# AlphaProtoRev3.net
KiCad netlist of a schematic drawn in EAGLE
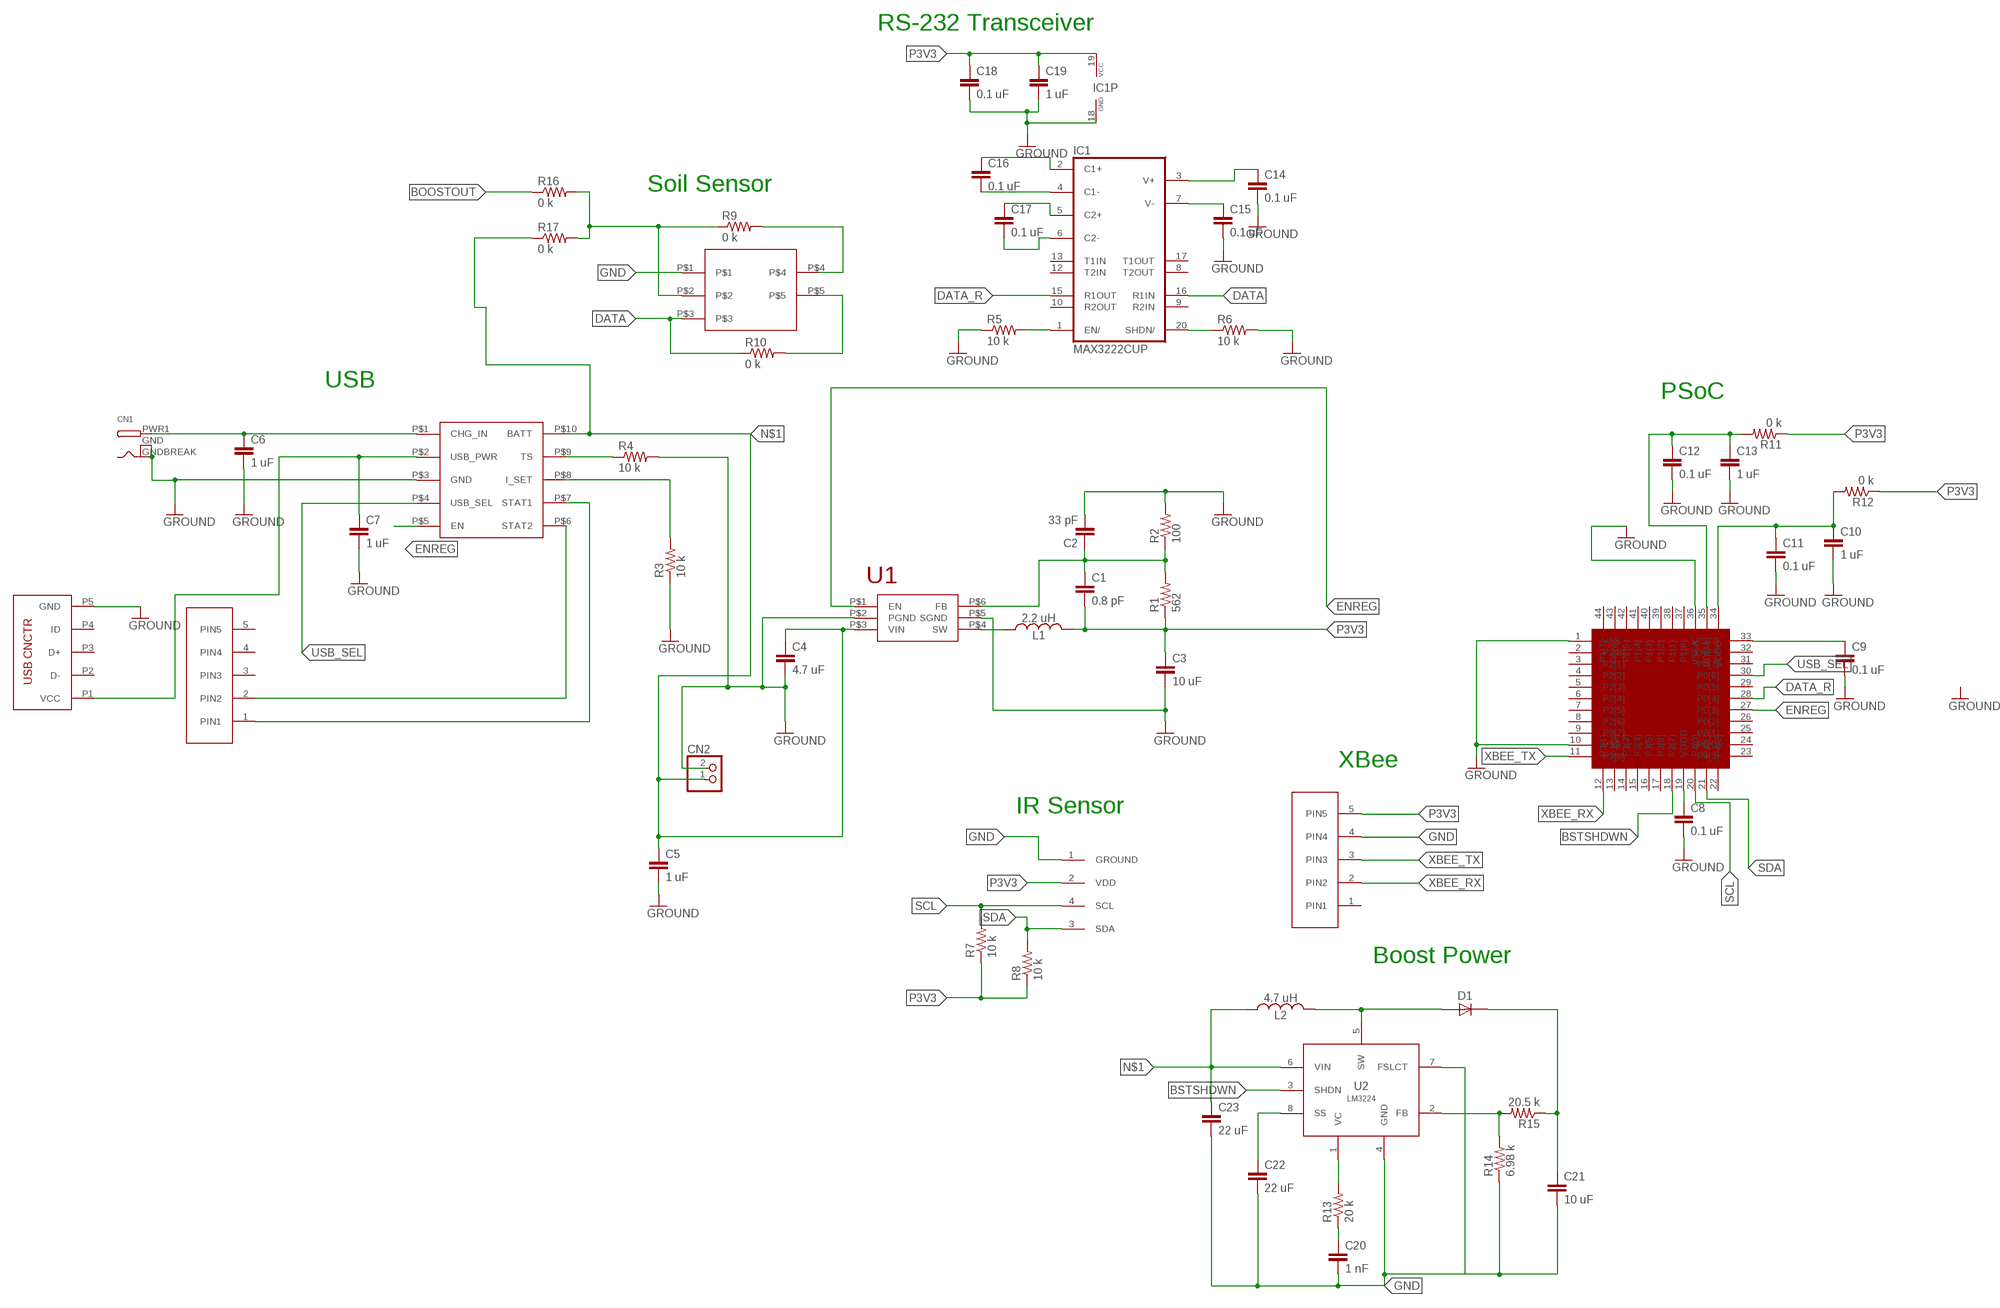
[diagram p0: schematic, sheet 1]

(export (version "E")
  (design (tool "Eeschema 10.0.6"))
  (components
    (comp (ref "C1")
      (value "0.8 pF")
      (footprint "eagle-import:0603")
      (libsource (lib "eagle-import") (part "CAPACITOR0603"))
    )
    (comp (ref "C2")
      (value "33 pF")
      (footprint "eagle-import:0603")
      (libsource (lib "eagle-import") (part "CAPACITOR0603"))
    )
    (comp (ref "C3")
      (value "10 uF")
      (footprint "eagle-import:0603")
      (libsource (lib "eagle-import") (part "CAPACITOR0603"))
    )
    (comp (ref "C4")
      (value "4.7 uF")
      (footprint "eagle-import:0603")
      (libsource (lib "eagle-import") (part "CAPACITOR0603"))
    )
    (comp (ref "C5")
      (value "1 uF")
      (footprint "eagle-import:0603")
      (libsource (lib "eagle-import") (part "CAPACITOR0603"))
    )
    (comp (ref "C6")
      (value "1 uF")
      (footprint "eagle-import:0603")
      (libsource (lib "eagle-import") (part "CAPACITOR0603"))
    )
    (comp (ref "C7")
      (value "1 uF")
      (footprint "eagle-import:0603")
      (libsource (lib "eagle-import") (part "CAPACITOR0603"))
    )
    (comp (ref "C8")
      (value "0.1 uF")
      (footprint "eagle-import:0603")
      (libsource (lib "eagle-import") (part "CAPACITOR0603"))
    )
    (comp (ref "C9")
      (value "0.1 uF")
      (footprint "eagle-import:0603")
      (libsource (lib "eagle-import") (part "CAPACITOR0603"))
    )
    (comp (ref "C10")
      (value "1 uF")
      (footprint "eagle-import:0603")
      (libsource (lib "eagle-import") (part "CAPACITOR0603"))
    )
    (comp (ref "C11")
      (value "0.1 uF")
      (footprint "eagle-import:0603")
      (libsource (lib "eagle-import") (part "CAPACITOR0603"))
    )
    (comp (ref "C12")
      (value "0.1 uF")
      (footprint "eagle-import:0603")
      (libsource (lib "eagle-import") (part "CAPACITOR0603"))
    )
    (comp (ref "C13")
      (value "1 uF")
      (footprint "eagle-import:0603")
      (libsource (lib "eagle-import") (part "CAPACITOR0603"))
    )
    (comp (ref "C14")
      (value "0.1 uF")
      (footprint "eagle-import:0603")
      (libsource (lib "eagle-import") (part "CAPACITOR0603"))
    )
    (comp (ref "C15")
      (value "0.1 uF")
      (footprint "eagle-import:0603")
      (libsource (lib "eagle-import") (part "CAPACITOR0603"))
    )
    (comp (ref "C16")
      (value "0.1 uF")
      (footprint "eagle-import:0603")
      (libsource (lib "eagle-import") (part "CAPACITOR0603"))
    )
    (comp (ref "C17")
      (value "0.1 uF")
      (footprint "eagle-import:0603")
      (libsource (lib "eagle-import") (part "CAPACITOR0603"))
    )
    (comp (ref "C18")
      (value "0.1 uF")
      (footprint "eagle-import:0603")
      (libsource (lib "eagle-import") (part "CAPACITOR0603"))
    )
    (comp (ref "C19")
      (value "1 uF")
      (footprint "eagle-import:0603")
      (libsource (lib "eagle-import") (part "CAPACITOR0603"))
    )
    (comp (ref "C20")
      (value "1 nF")
      (footprint "eagle-import:0603")
      (libsource (lib "eagle-import") (part "CAPACITOR0603"))
    )
    (comp (ref "C21")
      (value "10 uF")
      (footprint "eagle-import:0603")
      (libsource (lib "eagle-import") (part "CAPACITOR0603"))
    )
    (comp (ref "C22")
      (value "22 uF")
      (footprint "eagle-import:0603")
      (libsource (lib "eagle-import") (part "CAPACITOR0603"))
    )
    (comp (ref "C23")
      (value "22 uF")
      (footprint "eagle-import:0603")
      (libsource (lib "eagle-import") (part "CAPACITOR0603"))
    )
    (comp (ref "CN1")
      (value "DCBARRELSMT")
      (footprint "eagle-import:DCJACK_2MM_SMT")
      (libsource (lib "eagle-import") (part "DCBARRELSMT"))
    )
    (comp (ref "CN2")
      (value "JST_2PIN-SMT-RA")
      (footprint "eagle-import:JST-PH-2-SMT-RA")
      (libsource (lib "eagle-import") (part "JST_2PIN-SMT-RA"))
    )
    (comp (ref "D1")
      (value "DIODE")
      (footprint "eagle-import:0603-LED")
      (libsource (lib "eagle-import") (part "DIODE"))
    )
    (comp (ref "IC")
      (value "PSOC4FP")
      (footprint "eagle-import:TQFP44")
      (libsource (lib "eagle-import") (part "PSOC4FP"))
    )
    (comp (ref "IC1")
      (value "MAX3222CUP")
      (footprint "eagle-import:TSSOP20")
      (libsource (lib "eagle-import") (part "MAX3222CUP"))
    )
    (comp (ref "IRSENSOR")
      (value "TO39")
      (footprint "eagle-import:TO39")
      (libsource (lib "eagle-import") (part "TO39"))
    )
    (comp (ref "L1")
      (value "2.2 uH")
      (footprint "eagle-import:0603")
      (libsource (lib "eagle-import") (part "INDUCTOR0603"))
    )
    (comp (ref "L2")
      (value "4.7 uH")
      (footprint "eagle-import:0603")
      (libsource (lib "eagle-import") (part "INDUCTOR0603"))
    )
    (comp (ref "R1")
      (value "562")
      (footprint "eagle-import:0603")
      (libsource (lib "eagle-import") (part "RESISTOR0603"))
    )
    (comp (ref "R2")
      (value "100")
      (footprint "eagle-import:0603")
      (libsource (lib "eagle-import") (part "RESISTOR0603"))
    )
    (comp (ref "R3")
      (value "10 k")
      (footprint "eagle-import:0603")
      (libsource (lib "eagle-import") (part "RESISTOR0603"))
    )
    (comp (ref "R4")
      (value "10 k")
      (footprint "eagle-import:0603")
      (libsource (lib "eagle-import") (part "RESISTOR0603"))
    )
    (comp (ref "R5")
      (value "10 k")
      (footprint "eagle-import:0603")
      (libsource (lib "eagle-import") (part "RESISTOR0603"))
    )
    (comp (ref "R6")
      (value "10 k")
      (footprint "eagle-import:0603")
      (libsource (lib "eagle-import") (part "RESISTOR0603"))
    )
    (comp (ref "R7")
      (value "10 k")
      (footprint "eagle-import:0603")
      (libsource (lib "eagle-import") (part "RESISTOR0603"))
    )
    (comp (ref "R8")
      (value "10 k")
      (footprint "eagle-import:0603")
      (libsource (lib "eagle-import") (part "RESISTOR0603"))
    )
    (comp (ref "R9")
      (value "0 k")
      (footprint "eagle-import:0603")
      (libsource (lib "eagle-import") (part "RESISTOR0603"))
    )
    (comp (ref "R10")
      (value "0 k")
      (footprint "eagle-import:0603")
      (libsource (lib "eagle-import") (part "RESISTOR0603"))
    )
    (comp (ref "R11")
      (value "0 k")
      (footprint "eagle-import:0603")
      (libsource (lib "eagle-import") (part "RESISTOR0603"))
    )
    (comp (ref "R12")
      (value "0 k")
      (footprint "eagle-import:0603")
      (libsource (lib "eagle-import") (part "RESISTOR0603"))
    )
    (comp (ref "R13")
      (value "20 k")
      (footprint "eagle-import:0603")
      (libsource (lib "eagle-import") (part "RESISTOR0603"))
    )
    (comp (ref "R14")
      (value "6.98 k")
      (footprint "eagle-import:0603")
      (libsource (lib "eagle-import") (part "RESISTOR0603"))
    )
    (comp (ref "R15")
      (value "20.5 k")
      (footprint "eagle-import:0603")
      (libsource (lib "eagle-import") (part "RESISTOR0603"))
    )
    (comp (ref "R16")
      (value "0 k")
      (footprint "eagle-import:0603")
      (libsource (lib "eagle-import") (part "RESISTOR0603"))
    )
    (comp (ref "R17")
      (value "0 k")
      (footprint "eagle-import:0603")
      (libsource (lib "eagle-import") (part "RESISTOR0603"))
    )
    (comp (ref "U$2")
      (value "AUDIOJACK")
      (footprint "eagle-import:AUDIOJACK")
      (libsource (lib "eagle-import") (part "AUDIOJACK"))
    )
    (comp (ref "U$4")
      (value "LM3658")
      (footprint "eagle-import:LM3658")
      (libsource (lib "eagle-import") (part "LM3658"))
    )
    (comp (ref "U$7")
      (value "FCI10118192-0001LF")
      (footprint "eagle-import:FCI10118192-0001LF")
      (libsource (lib "eagle-import") (part "FCI10118192-0001LF"))
    )
    (comp (ref "U1")
      (value "LM3671-407564")
      (footprint "eagle-import:LM3671-407564")
      (libsource (lib "eagle-import") (part "LM3671-407564"))
    )
    (comp (ref "U2")
      (value "LM3224")
      (footprint "eagle-import:MSOP-8")
      (libsource (lib "eagle-import") (part "LM3224"))
    )
    (comp (ref "USB")
      (value "HEADER-5")
      (footprint "eagle-import:NON-5")
      (libsource (lib "eagle-import") (part "HEADER-5"))
    )
    (comp (ref "XBEE")
      (value "HEADER-5")
      (footprint "eagle-import:NON-5")
      (libsource (lib "eagle-import") (part "HEADER-5"))
    )
  )
  (nets
    (net (code "1") (name "BOOSTOUT") (class "Default")
      (node (ref "C21") (pin "1") (pinfunction "1_1") (pintype "passive"))
      (node (ref "D1") (pin "C") (pinfunction "C_C") (pintype "passive"))
      (node (ref "R15") (pin "1") (pinfunction "1_1") (pintype "passive"))
      (node (ref "R16") (pin "1") (pinfunction "1_1") (pintype "passive"))
    )
    (net (code "2") (name "BSTSHDWN") (class "Default")
      (node (ref "IC") (pin "18") (pinfunction "P3[7]_18") (pintype "bidirectional"))
      (node (ref "U2") (pin "3") (pinfunction "SHDN_3") (pintype "bidirectional"))
    )
    (net (code "3") (name "DATA") (class "Default")
      (node (ref "IC1") (pin "16") (pinfunction "R1IN_16") (pintype "input"))
      (node (ref "R10") (pin "1") (pinfunction "1_1") (pintype "passive"))
      (node (ref "U$2") (pin "P$3") (pinfunction "P$3_P$3") (pintype "output"))
    )
    (net (code "4") (name "DATA_R") (class "Default")
      (node (ref "IC") (pin "28") (pinfunction "P0[4]_28") (pintype "bidirectional"))
      (node (ref "IC1") (pin "15") (pinfunction "R1OUT_15") (pintype "output"))
    )
    (net (code "5") (name "ENREG") (class "Default")
      (node (ref "IC") (pin "27") (pinfunction "P0[3]_27") (pintype "bidirectional"))
      (node (ref "U$4") (pin "P$5") (pinfunction "EN_P$5") (pintype "input"))
      (node (ref "U1") (pin "P$1") (pinfunction "EN_P$1") (pintype "bidirectional"))
    )
    (net (code "6") (name "GND") (class "Default")
      (node (ref "C10") (pin "2") (pinfunction "2_2") (pintype "passive"))
      (node (ref "C11") (pin "2") (pinfunction "2_2") (pintype "passive"))
      (node (ref "C12") (pin "2") (pinfunction "2_2") (pintype "passive"))
      (node (ref "C13") (pin "2") (pinfunction "2_2") (pintype "passive"))
      (node (ref "C14") (pin "2") (pinfunction "2_2") (pintype "passive"))
      (node (ref "C15") (pin "2") (pinfunction "2_2") (pintype "passive"))
      (node (ref "C18") (pin "2") (pinfunction "2_2") (pintype "passive"))
      (node (ref "C19") (pin "2") (pinfunction "2_2") (pintype "passive"))
      (node (ref "C2") (pin "2") (pinfunction "2_2") (pintype "passive"))
      (node (ref "C20") (pin "2") (pinfunction "2_2") (pintype "passive"))
      (node (ref "C21") (pin "2") (pinfunction "2_2") (pintype "passive"))
      (node (ref "C22") (pin "2") (pinfunction "2_2") (pintype "passive"))
      (node (ref "C23") (pin "2") (pinfunction "2_2") (pintype "passive"))
      (node (ref "C3") (pin "2") (pinfunction "2_2") (pintype "passive"))
      (node (ref "C4") (pin "2") (pinfunction "2_2") (pintype "passive"))
      (node (ref "C5") (pin "2") (pinfunction "2_2") (pintype "passive"))
      (node (ref "C6") (pin "2") (pinfunction "2_2") (pintype "passive"))
      (node (ref "C7") (pin "2") (pinfunction "2_2") (pintype "passive"))
      (node (ref "C8") (pin "2") (pinfunction "2_2") (pintype "passive"))
      (node (ref "C9") (pin "2") (pinfunction "2_2") (pintype "passive"))
      (node (ref "CN1") (pin "GND") (pinfunction "GNDBREAK_GND") (pintype "power_in"))
      (node (ref "CN1") (pin "GNDBREAK") (pinfunction "GND_GNDBREAK") (pintype "power_in"))
      (node (ref "CN2") (pin "2") (pinfunction "1_2") (pintype "passive"))
      (node (ref "IC") (pin "1") (pinfunction "VSS_1") (pintype "bidirectional"))
      (node (ref "IC") (pin "10") (pinfunction "VSS_10") (pintype "bidirectional"))
      (node (ref "IC") (pin "36") (pinfunction "VSSA_36") (pintype "bidirectional"))
      (node (ref "IC1") (pin "18") (pinfunction "GND_18") (pintype "power_in"))
      (node (ref "IRSENSOR") (pin "1") (pinfunction "GROUND_1") (pintype "bidirectional"))
      (node (ref "R14") (pin "1") (pinfunction "1_1") (pintype "passive"))
      (node (ref "R2") (pin "2") (pinfunction "2_2") (pintype "passive"))
      (node (ref "R3") (pin "1") (pinfunction "1_1") (pintype "passive"))
      (node (ref "R4") (pin "2") (pinfunction "2_2") (pintype "passive"))
      (node (ref "R5") (pin "1") (pinfunction "1_1") (pintype "passive"))
      (node (ref "R6") (pin "2") (pinfunction "2_2") (pintype "passive"))
      (node (ref "U$2") (pin "P$1") (pinfunction "P$1_P$1") (pintype "output"))
      (node (ref "U$4") (pin "P$3") (pinfunction "GND_P$3") (pintype "power_in"))
      (node (ref "U$7") (pin "P5") (pinfunction "GND_P5") (pintype "power_in"))
      (node (ref "U1") (pin "P$2") (pinfunction "PGND_P$2") (pintype "passive"))
      (node (ref "U1") (pin "P$5") (pinfunction "SGND_P$5") (pintype "power_in"))
      (node (ref "U2") (pin "4") (pinfunction "GND_4") (pintype "bidirectional"))
      (node (ref "U2") (pin "7") (pinfunction "FSLCT_7") (pintype "bidirectional"))
      (node (ref "XBEE") (pin "4") (pinfunction "PIN4_4") (pintype "bidirectional"))
    )
    (net (code "7") (name "N$1") (class "Default")
      (node (ref "C23") (pin "1") (pinfunction "1_1") (pintype "passive"))
      (node (ref "C4") (pin "1") (pinfunction "1_1") (pintype "passive"))
      (node (ref "C5") (pin "1") (pinfunction "1_1") (pintype "passive"))
      (node (ref "CN2") (pin "1") (pinfunction "2_1") (pintype "passive"))
      (node (ref "L2") (pin "1") (pinfunction "1_1") (pintype "passive"))
      (node (ref "R17") (pin "1") (pinfunction "1_1") (pintype "passive"))
      (node (ref "U$4") (pin "P$10") (pinfunction "BATT_P$10") (pintype "power_in"))
      (node (ref "U1") (pin "P$3") (pinfunction "VIN_P$3") (pintype "power_in"))
      (node (ref "U2") (pin "6") (pinfunction "VIN_6") (pintype "bidirectional"))
    )
    (net (code "8") (name "Net-(C8-Pad1)") (class "Default")
      (node (ref "C8") (pin "1") (pinfunction "1_1") (pintype "passive"))
      (node (ref "IC") (pin "19") (pinfunction "VDDD_19") (pintype "bidirectional"))
    )
    (net (code "9") (name "Net-(C10-Pad1)") (class "Default")
      (node (ref "C10") (pin "1") (pinfunction "1_1") (pintype "passive"))
      (node (ref "C11") (pin "1") (pinfunction "1_1") (pintype "passive"))
      (node (ref "IC") (pin "34") (pinfunction "VDDD_34") (pintype "bidirectional"))
      (node (ref "R12") (pin "2") (pinfunction "2_2") (pintype "passive"))
    )
    (net (code "10") (name "Net-(C20-Pad1)") (class "Default")
      (node (ref "C20") (pin "1") (pinfunction "1_1") (pintype "passive"))
      (node (ref "R13") (pin "1") (pinfunction "1_1") (pintype "passive"))
    )
    (net (code "11") (name "Net-(CN1-PWR)") (class "Default")
      (node (ref "C6") (pin "1") (pinfunction "1_1") (pintype "passive"))
      (node (ref "CN1") (pin "PWR1") (pinfunction "PWR_PWR1") (pintype "power_in"))
      (node (ref "U$4") (pin "P$1") (pinfunction "CHG_IN_P$1") (pintype "power_in"))
    )
    (net (code "12") (name "Net-(IC-VCCD)") (class "Default")
      (node (ref "C9") (pin "1") (pinfunction "1_1") (pintype "passive"))
      (node (ref "IC") (pin "33") (pinfunction "VCCD_33") (pintype "bidirectional"))
    )
    (net (code "13") (name "Net-(IC-VDDA)") (class "Default")
      (node (ref "C12") (pin "1") (pinfunction "1_1") (pintype "passive"))
      (node (ref "C13") (pin "1") (pinfunction "1_1") (pintype "passive"))
      (node (ref "IC") (pin "35") (pinfunction "VDDA_35") (pintype "bidirectional"))
      (node (ref "R11") (pin "2") (pinfunction "2_2") (pintype "passive"))
    )
    (net (code "14") (name "Net-(IC1A-C1+)") (class "Default")
      (node (ref "C16") (pin "1") (pinfunction "1_1") (pintype "passive"))
      (node (ref "IC1") (pin "2") (pinfunction "C1+_2") (pintype "passive"))
    )
    (net (code "15") (name "Net-(IC1A-C1-)") (class "Default")
      (node (ref "C16") (pin "2") (pinfunction "2_2") (pintype "passive"))
      (node (ref "IC1") (pin "4") (pinfunction "C1-_4") (pintype "passive"))
    )
    (net (code "16") (name "Net-(IC1A-C2+)") (class "Default")
      (node (ref "C17") (pin "1") (pinfunction "1_1") (pintype "passive"))
      (node (ref "IC1") (pin "5") (pinfunction "C2+_5") (pintype "passive"))
    )
    (net (code "17") (name "Net-(IC1A-C2-)") (class "Default")
      (node (ref "C17") (pin "2") (pinfunction "2_2") (pintype "passive"))
      (node (ref "IC1") (pin "6") (pinfunction "C2-_6") (pintype "passive"))
    )
    (net (code "18") (name "Net-(IC1A-EN{slash})") (class "Default")
      (node (ref "IC1") (pin "1") (pinfunction "EN/_1") (pintype "input"))
      (node (ref "R5") (pin "2") (pinfunction "2_2") (pintype "passive"))
    )
    (net (code "19") (name "Net-(IC1A-SHDN{slash})") (class "Default")
      (node (ref "IC1") (pin "20") (pinfunction "SHDN/_20") (pintype "input"))
      (node (ref "R6") (pin "1") (pinfunction "1_1") (pintype "passive"))
    )
    (net (code "20") (name "Net-(IC1A-V+)") (class "Default")
      (node (ref "C14") (pin "1") (pinfunction "1_1") (pintype "passive"))
      (node (ref "IC1") (pin "3") (pinfunction "V+_3") (pintype "passive"))
    )
    (net (code "21") (name "Net-(IC1A-V-)") (class "Default")
      (node (ref "C15") (pin "1") (pinfunction "1_1") (pintype "passive"))
      (node (ref "IC1") (pin "7") (pinfunction "V-_7") (pintype "passive"))
    )
    (net (code "22") (name "Net-(R9-Pad2)") (class "Default")
      (node (ref "R9") (pin "2") (pinfunction "2_2") (pintype "passive"))
      (node (ref "U$2") (pin "P$4") (pinfunction "P$4_P$4") (pintype "output"))
    )
    (net (code "23") (name "Net-(R10-Pad2)") (class "Default")
      (node (ref "R10") (pin "2") (pinfunction "2_2") (pintype "passive"))
      (node (ref "U$2") (pin "P$5") (pinfunction "P$5_P$5") (pintype "output"))
    )
    (net (code "24") (name "Net-(R16-Pad2)") (class "Default")
      (node (ref "R16") (pin "2") (pinfunction "2_2") (pintype "passive"))
      (node (ref "R17") (pin "2") (pinfunction "2_2") (pintype "passive"))
      (node (ref "R9") (pin "1") (pinfunction "1_1") (pintype "passive"))
      (node (ref "U$2") (pin "P$2") (pinfunction "P$2_P$2") (pintype "output"))
    )
    (net (code "25") (name "Net-(U$4-I_SET)") (class "Default")
      (node (ref "R3") (pin "2") (pinfunction "2_2") (pintype "passive"))
      (node (ref "U$4") (pin "P$8") (pinfunction "I_SET_P$8") (pintype "bidirectional"))
    )
    (net (code "26") (name "Net-(U$4-STAT1)") (class "Default")
      (node (ref "U$4") (pin "P$7") (pinfunction "STAT1_P$7") (pintype "output"))
      (node (ref "USB") (pin "1") (pinfunction "PIN1_1") (pintype "bidirectional"))
    )
    (net (code "27") (name "Net-(U$4-STAT2)") (class "Default")
      (node (ref "U$4") (pin "P$6") (pinfunction "STAT2_P$6") (pintype "output"))
      (node (ref "USB") (pin "2") (pinfunction "PIN2_2") (pintype "bidirectional"))
    )
    (net (code "28") (name "Net-(U$4-TS)") (class "Default")
      (node (ref "R4") (pin "1") (pinfunction "1_1") (pintype "passive"))
      (node (ref "U$4") (pin "P$9") (pinfunction "TS_P$9") (pintype "bidirectional"))
    )
    (net (code "29") (name "Net-(U$4-USB_PWR)") (class "Default")
      (node (ref "C7") (pin "1") (pinfunction "1_1") (pintype "passive"))
      (node (ref "U$4") (pin "P$2") (pinfunction "USB_PWR_P$2") (pintype "power_in"))
      (node (ref "U$7") (pin "P1") (pinfunction "VCC_P1") (pintype "power_in"))
    )
    (net (code "30") (name "Net-(U1-FB)") (class "Default")
      (node (ref "C1") (pin "1") (pinfunction "1_1") (pintype "passive"))
      (node (ref "C2") (pin "1") (pinfunction "1_1") (pintype "passive"))
      (node (ref "R1") (pin "2") (pinfunction "2_2") (pintype "passive"))
      (node (ref "R2") (pin "1") (pinfunction "1_1") (pintype "passive"))
      (node (ref "U1") (pin "P$6") (pinfunction "FB_P$6") (pintype "bidirectional"))
    )
    (net (code "31") (name "Net-(U1-SW)") (class "Default")
      (node (ref "L1") (pin "1") (pinfunction "1_1") (pintype "passive"))
      (node (ref "U1") (pin "P$4") (pinfunction "SW_P$4") (pintype "bidirectional"))
    )
    (net (code "32") (name "Net-(U2-FB)") (class "Default")
      (node (ref "R14") (pin "2") (pinfunction "2_2") (pintype "passive"))
      (node (ref "R15") (pin "2") (pinfunction "2_2") (pintype "passive"))
      (node (ref "U2") (pin "2") (pinfunction "FB_2") (pintype "bidirectional"))
    )
    (net (code "33") (name "Net-(U2-SS)") (class "Default")
      (node (ref "C22") (pin "1") (pinfunction "1_1") (pintype "passive"))
      (node (ref "U2") (pin "8") (pinfunction "SS_8") (pintype "bidirectional"))
    )
    (net (code "34") (name "Net-(U2-SW)") (class "Default")
      (node (ref "D1") (pin "A") (pinfunction "A_A") (pintype "passive"))
      (node (ref "L2") (pin "2") (pinfunction "2_2") (pintype "passive"))
      (node (ref "U2") (pin "5") (pinfunction "SW_5") (pintype "bidirectional"))
    )
    (net (code "35") (name "Net-(U2-VC)") (class "Default")
      (node (ref "R13") (pin "2") (pinfunction "2_2") (pintype "passive"))
      (node (ref "U2") (pin "1") (pinfunction "VC_1") (pintype "bidirectional"))
    )
    (net (code "36") (name "P3V3") (class "Default")
      (node (ref "C1") (pin "2") (pinfunction "2_2") (pintype "passive"))
      (node (ref "C18") (pin "1") (pinfunction "1_1") (pintype "passive"))
      (node (ref "C19") (pin "1") (pinfunction "1_1") (pintype "passive"))
      (node (ref "C3") (pin "1") (pinfunction "1_1") (pintype "passive"))
      (node (ref "IC1") (pin "19") (pinfunction "VCC_19") (pintype "power_in"))
      (node (ref "IRSENSOR") (pin "2") (pinfunction "VDD_2") (pintype "bidirectional"))
      (node (ref "L1") (pin "2") (pinfunction "2_2") (pintype "passive"))
      (node (ref "R1") (pin "1") (pinfunction "1_1") (pintype "passive"))
      (node (ref "R11") (pin "1") (pinfunction "1_1") (pintype "passive"))
      (node (ref "R12") (pin "1") (pinfunction "1_1") (pintype "passive"))
      (node (ref "R7") (pin "1") (pinfunction "1_1") (pintype "passive"))
      (node (ref "R8") (pin "1") (pinfunction "1_1") (pintype "passive"))
      (node (ref "XBEE") (pin "5") (pinfunction "PIN5_5") (pintype "bidirectional"))
    )
    (net (code "37") (name "SCL") (class "Default")
      (node (ref "IC") (pin "20") (pinfunction "P4[0]_20") (pintype "bidirectional"))
      (node (ref "IRSENSOR") (pin "4") (pinfunction "SCL_4") (pintype "bidirectional"))
      (node (ref "R7") (pin "2") (pinfunction "2_2") (pintype "passive"))
    )
    (net (code "38") (name "SDA") (class "Default")
      (node (ref "IC") (pin "21") (pinfunction "P4[1]_21") (pintype "bidirectional"))
      (node (ref "IRSENSOR") (pin "3") (pinfunction "SDA_3") (pintype "bidirectional"))
      (node (ref "R8") (pin "2") (pinfunction "2_2") (pintype "passive"))
    )
    (net (code "39") (name "USB_SEL") (class "Default")
      (node (ref "IC") (pin "30") (pinfunction "P0[6]_30") (pintype "bidirectional"))
      (node (ref "U$4") (pin "P$4") (pinfunction "USB_SEL_P$4") (pintype "input"))
    )
    (net (code "40") (name "XBEE_RX") (class "Default")
      (node (ref "IC") (pin "12") (pinfunction "P3[1]_12") (pintype "bidirectional"))
      (node (ref "XBEE") (pin "2") (pinfunction "PIN2_2") (pintype "bidirectional"))
    )
    (net (code "41") (name "XBEE_TX") (class "Default")
      (node (ref "IC") (pin "11") (pinfunction "P3[0]_11") (pintype "bidirectional"))
      (node (ref "XBEE") (pin "3") (pinfunction "PIN3_3") (pintype "bidirectional"))
    )
    (net (code "42") (name "unconnected-(IC-P0[0]-Pad24)") (class "Default")
      (node (ref "IC") (pin "24") (pinfunction "P0[0]_24") (pintype "bidirectional"))
    )
    (net (code "43") (name "unconnected-(IC-P0[1]-Pad25)") (class "Default")
      (node (ref "IC") (pin "25") (pinfunction "P0[1]_25") (pintype "bidirectional"))
    )
    (net (code "44") (name "unconnected-(IC-P0[2]-Pad26)") (class "Default")
      (node (ref "IC") (pin "26") (pinfunction "P0[2]_26") (pintype "bidirectional"))
    )
    (net (code "45") (name "unconnected-(IC-P0[5]-Pad29)") (class "Default")
      (node (ref "IC") (pin "29") (pinfunction "P0[5]_29") (pintype "bidirectional"))
    )
    (net (code "46") (name "unconnected-(IC-P0[7]-Pad31)") (class "Default")
      (node (ref "IC") (pin "31") (pinfunction "P0[7]_31") (pintype "bidirectional"))
    )
    (net (code "47") (name "unconnected-(IC-P1[0]-Pad37)") (class "Default")
      (node (ref "IC") (pin "37") (pinfunction "P1[0]_37") (pintype "bidirectional"))
    )
    (net (code "48") (name "unconnected-(IC-P1[1]-Pad38)") (class "Default")
      (node (ref "IC") (pin "38") (pinfunction "P1[1]_38") (pintype "bidirectional"))
    )
    (net (code "49") (name "unconnected-(IC-P1[2]-Pad39)") (class "Default")
      (node (ref "IC") (pin "39") (pinfunction "P1[2]_39") (pintype "bidirectional"))
    )
    (net (code "50") (name "unconnected-(IC-P1[3]-Pad40)") (class "Default")
      (node (ref "IC") (pin "40") (pinfunction "P1[3]_40") (pintype "bidirectional"))
    )
    (net (code "51") (name "unconnected-(IC-P1[4]-Pad41)") (class "Default")
      (node (ref "IC") (pin "41") (pinfunction "P1[4]_41") (pintype "bidirectional"))
    )
    (net (code "52") (name "unconnected-(IC-P1[5]-Pad42)") (class "Default")
      (node (ref "IC") (pin "42") (pinfunction "P1[5]_42") (pintype "bidirectional"))
    )
    (net (code "53") (name "unconnected-(IC-P1[6]-Pad43)") (class "Default")
      (node (ref "IC") (pin "43") (pinfunction "P1[6]_43") (pintype "bidirectional"))
    )
    (net (code "54") (name "unconnected-(IC-P1[7]-Pad44)") (class "Default")
      (node (ref "IC") (pin "44") (pinfunction "P1[7]_44") (pintype "bidirectional"))
    )
    (net (code "55") (name "unconnected-(IC-P2[0]-Pad2)") (class "Default")
      (node (ref "IC") (pin "2") (pinfunction "P2[0]_2") (pintype "bidirectional"))
    )
    (net (code "56") (name "unconnected-(IC-P2[1]-Pad3)") (class "Default")
      (node (ref "IC") (pin "3") (pinfunction "P2[1]_3") (pintype "bidirectional"))
    )
    (net (code "57") (name "unconnected-(IC-P2[2]-Pad4)") (class "Default")
      (node (ref "IC") (pin "4") (pinfunction "P2[2]_4") (pintype "bidirectional"))
    )
    (net (code "58") (name "unconnected-(IC-P2[3]-Pad5)") (class "Default")
      (node (ref "IC") (pin "5") (pinfunction "P2[3]_5") (pintype "bidirectional"))
    )
    (net (code "59") (name "unconnected-(IC-P2[4]-Pad6)") (class "Default")
      (node (ref "IC") (pin "6") (pinfunction "P2[4]_6") (pintype "bidirectional"))
    )
    (net (code "60") (name "unconnected-(IC-P2[5]-Pad7)") (class "Default")
      (node (ref "IC") (pin "7") (pinfunction "P2[5]_7") (pintype "bidirectional"))
    )
    (net (code "61") (name "unconnected-(IC-P2[6]-Pad8)") (class "Default")
      (node (ref "IC") (pin "8") (pinfunction "P2[6]_8") (pintype "bidirectional"))
    )
    (net (code "62") (name "unconnected-(IC-P2[7]-Pad9)") (class "Default")
      (node (ref "IC") (pin "9") (pinfunction "P2[7]_9") (pintype "bidirectional"))
    )
    (net (code "63") (name "unconnected-(IC-P3[2]-Pad13)") (class "Default")
      (node (ref "IC") (pin "13") (pinfunction "P3[2]_13") (pintype "bidirectional"))
    )
    (net (code "64") (name "unconnected-(IC-P3[3]-Pad14)") (class "Default")
      (node (ref "IC") (pin "14") (pinfunction "P3[3]_14") (pintype "bidirectional"))
    )
    (net (code "65") (name "unconnected-(IC-P3[4]-Pad15)") (class "Default")
      (node (ref "IC") (pin "15") (pinfunction "P3[4]_15") (pintype "bidirectional"))
    )
    (net (code "66") (name "unconnected-(IC-P3[5]-Pad16)") (class "Default")
      (node (ref "IC") (pin "16") (pinfunction "P3[5]_16") (pintype "bidirectional"))
    )
    (net (code "67") (name "unconnected-(IC-P3[6]-Pad17)") (class "Default")
      (node (ref "IC") (pin "17") (pinfunction "P3[6]_17") (pintype "bidirectional"))
    )
    (net (code "68") (name "unconnected-(IC-P4[2]-Pad22)") (class "Default")
      (node (ref "IC") (pin "22") (pinfunction "P4[2]_22") (pintype "bidirectional"))
    )
    (net (code "69") (name "unconnected-(IC-P4[3]-Pad23)") (class "Default")
      (node (ref "IC") (pin "23") (pinfunction "P4[3]_23") (pintype "bidirectional"))
    )
    (net (code "70") (name "unconnected-(IC-XRES-Pad32)") (class "Default")
      (node (ref "IC") (pin "32") (pinfunction "XRES_32") (pintype "bidirectional"))
    )
    (net (code "71") (name "unconnected-(IC1A-R2IN-Pad9)") (class "Default")
      (node (ref "IC1") (pin "9") (pinfunction "R2IN_9") (pintype "input"))
    )
    (net (code "72") (name "unconnected-(IC1A-R2OUT-Pad10)") (class "Default")
      (node (ref "IC1") (pin "10") (pinfunction "R2OUT_10") (pintype "output"))
    )
    (net (code "73") (name "unconnected-(IC1A-T1IN-Pad13)") (class "Default")
      (node (ref "IC1") (pin "13") (pinfunction "T1IN_13") (pintype "input"))
    )
    (net (code "74") (name "unconnected-(IC1A-T1OUT-Pad17)") (class "Default")
      (node (ref "IC1") (pin "17") (pinfunction "T1OUT_17") (pintype "output"))
    )
    (net (code "75") (name "unconnected-(IC1A-T2IN-Pad12)") (class "Default")
      (node (ref "IC1") (pin "12") (pinfunction "T2IN_12") (pintype "input"))
    )
    (net (code "76") (name "unconnected-(IC1A-T2OUT-Pad8)") (class "Default")
      (node (ref "IC1") (pin "8") (pinfunction "T2OUT_8") (pintype "output"))
    )
    (net (code "77") (name "unconnected-(U$7-D+-PadP3)") (class "Default")
      (node (ref "U$7") (pin "P3") (pinfunction "D+_P3") (pintype "bidirectional"))
    )
    (net (code "78") (name "unconnected-(U$7-D--PadP2)") (class "Default")
      (node (ref "U$7") (pin "P2") (pinfunction "D-_P2") (pintype "bidirectional"))
    )
    (net (code "79") (name "unconnected-(U$7-ID-PadP4)") (class "Default")
      (node (ref "U$7") (pin "P4") (pinfunction "ID_P4") (pintype "bidirectional"))
    )
    (net (code "80") (name "unconnected-(USB-PIN3-Pad3)") (class "Default")
      (node (ref "USB") (pin "3") (pinfunction "PIN3_3") (pintype "bidirectional"))
    )
    (net (code "81") (name "unconnected-(USB-PIN4-Pad4)") (class "Default")
      (node (ref "USB") (pin "4") (pinfunction "PIN4_4") (pintype "bidirectional"))
    )
    (net (code "82") (name "unconnected-(USB-PIN5-Pad5)") (class "Default")
      (node (ref "USB") (pin "5") (pinfunction "PIN5_5") (pintype "bidirectional"))
    )
    (net (code "83") (name "unconnected-(XBEE-PIN1-Pad1)") (class "Default")
      (node (ref "XBEE") (pin "1") (pinfunction "PIN1_1") (pintype "bidirectional"))
    )
  )
)
